# motor-1.net
KiCad netlist of a schematic drawn in EAGLE
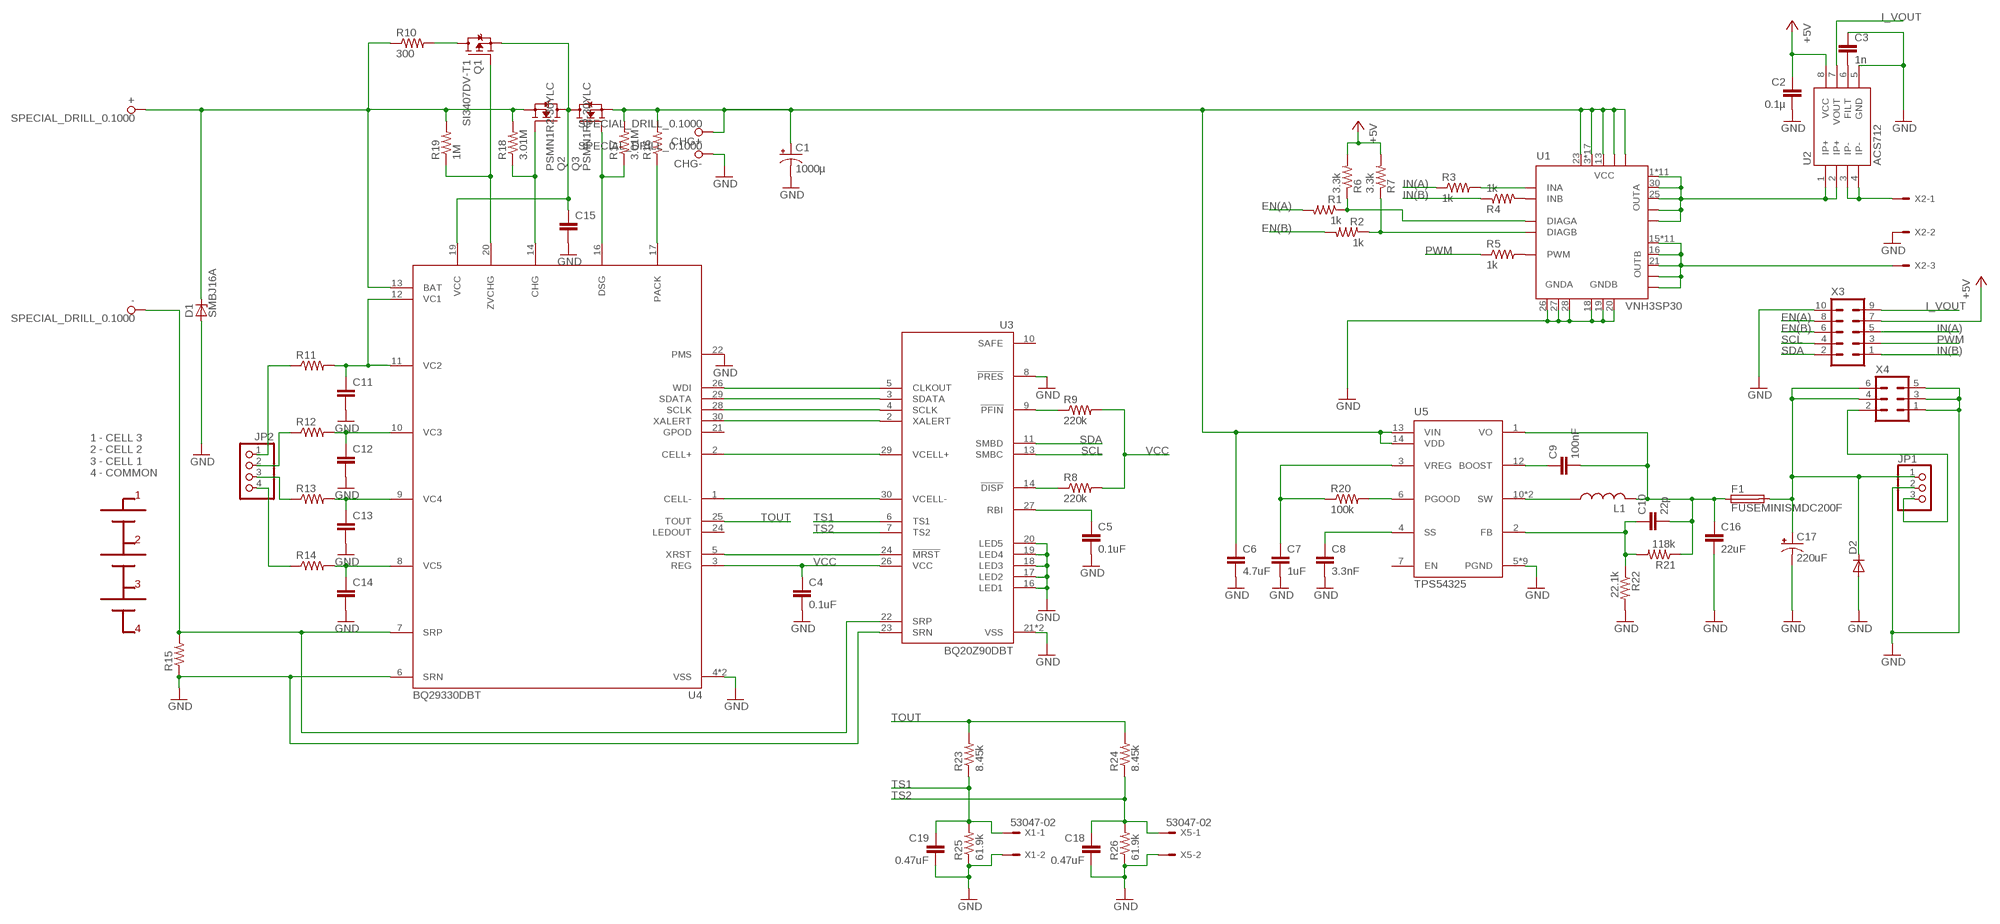
[diagram p0: schematic, sheet 1]

(export (version "E")
  (design (tool "Eeschema 10.0.6"))
  (components
    (comp (ref "+")
      (value "SPECIAL_DRILL_0.1000")
      (footprint "eagle-import:PAD_0.1000")
      (libsource (lib "eagle-import") (part "SPECIAL_DRILL_0.1000"))
    )
    (comp (ref "-")
      (value "SPECIAL_DRILL_0.1000")
      (footprint "eagle-import:PAD_0.1000")
      (libsource (lib "eagle-import") (part "SPECIAL_DRILL_0.1000"))
    )
    (comp (ref "C1")
      (value "1000µ")
      (footprint "eagle-import:E5-13")
      (libsource (lib "eagle-import") (part "CPOL-USE5-13"))
    )
    (comp (ref "C2")
      (value "0.1µ")
      (footprint "eagle-import:C0805")
      (libsource (lib "eagle-import") (part "C-EUC0805"))
    )
    (comp (ref "C3")
      (value "1n")
      (footprint "eagle-import:C0805")
      (libsource (lib "eagle-import") (part "C-EUC0805"))
    )
    (comp (ref "C4")
      (value "0.1uF")
      (footprint "eagle-import:C0603")
      (libsource (lib "eagle-import") (part "C-EUC0603"))
    )
    (comp (ref "C5")
      (value "0.1uF")
      (footprint "eagle-import:C0603")
      (libsource (lib "eagle-import") (part "C-EUC0603"))
    )
    (comp (ref "C6")
      (value "4.7uF")
      (footprint "eagle-import:C1206")
      (libsource (lib "eagle-import") (part "C-EUC1206"))
    )
    (comp (ref "C7")
      (value "1uF")
      (footprint "eagle-import:C0805")
      (libsource (lib "eagle-import") (part "C-EUC0805"))
    )
    (comp (ref "C8")
      (value "3.3nF")
      (footprint "eagle-import:C0805")
      (libsource (lib "eagle-import") (part "C-EUC0805"))
    )
    (comp (ref "C9")
      (value "100nF")
      (footprint "eagle-import:C0805")
      (libsource (lib "eagle-import") (part "C-EUC0805"))
    )
    (comp (ref "C10")
      (value "22p")
      (footprint "eagle-import:C0805")
      (libsource (lib "eagle-import") (part "C-EUC0805"))
    )
    (comp (ref "C11")
      (value "C-EUC0603")
      (footprint "eagle-import:C0603")
      (libsource (lib "eagle-import") (part "C-EUC0603"))
    )
    (comp (ref "C12")
      (value "C-EUC0603")
      (footprint "eagle-import:C0603")
      (libsource (lib "eagle-import") (part "C-EUC0603"))
    )
    (comp (ref "C13")
      (value "C-EUC0603")
      (footprint "eagle-import:C0603")
      (libsource (lib "eagle-import") (part "C-EUC0603"))
    )
    (comp (ref "C14")
      (value "C-EUC0603")
      (footprint "eagle-import:C0603")
      (libsource (lib "eagle-import") (part "C-EUC0603"))
    )
    (comp (ref "C15")
      (value "C-EUC0603")
      (footprint "eagle-import:C0603")
      (libsource (lib "eagle-import") (part "C-EUC0603"))
    )
    (comp (ref "C16")
      (value "22uF")
      (footprint "eagle-import:C3225")
      (libsource (lib "eagle-import") (part "C-EUC3225"))
    )
    (comp (ref "C17")
      (value "220uF")
      (footprint "eagle-import:E3,5-8")
      (libsource (lib "eagle-import") (part "CPOL-USE3.5-8"))
    )
    (comp (ref "C18")
      (value "0.47uF")
      (footprint "eagle-import:C0603")
      (libsource (lib "eagle-import") (part "C-EUC0603"))
    )
    (comp (ref "C19")
      (value "0.47uF")
      (footprint "eagle-import:C0603")
      (libsource (lib "eagle-import") (part "C-EUC0603"))
    )
    (comp (ref "CHG+")
      (value "SPECIAL_DRILL_0.1000")
      (footprint "eagle-import:PAD_0.1000")
      (libsource (lib "eagle-import") (part "SPECIAL_DRILL_0.1000"))
    )
    (comp (ref "CHG-")
      (value "SPECIAL_DRILL_0.1000")
      (footprint "eagle-import:PAD_0.1000")
      (libsource (lib "eagle-import") (part "SPECIAL_DRILL_0.1000"))
    )
    (comp (ref "D1")
      (value "SMBJ16A")
      (footprint "eagle-import:SMB")
      (libsource (lib "eagle-import") (part "ZENER-DIODESMB"))
    )
    (comp (ref "D2")
      (value "DIODE-DO214AC")
      (footprint "eagle-import:DO214AC")
      (libsource (lib "eagle-import") (part "DIODE-DO214AC"))
    )
    (comp (ref "F1")
      (value "FUSEMINISMDC200F")
      (footprint "eagle-import:MINISMDC200F")
      (libsource (lib "eagle-import") (part "FUSEMINISMDC200F"))
    )
    (comp (ref "JP1")
      (value "PINHD-1X3")
      (footprint "eagle-import:1X03")
      (libsource (lib "eagle-import") (part "PINHD-1X3"))
    )
    (comp (ref "JP2")
      (value "PINHD-1X4")
      (footprint "eagle-import:1X04")
      (libsource (lib "eagle-import") (part "PINHD-1X4"))
    )
    (comp (ref "L1")
      (value "L-USXAL50XX")
      (footprint "eagle-import:XAL50XX")
      (libsource (lib "eagle-import") (part "L-USXAL50XX"))
    )
    (comp (ref "Q1")
      (value "SI3407DV-T1")
      (footprint "eagle-import:SOT23-6")
      (libsource (lib "eagle-import") (part "SI3407DV-T1"))
    )
    (comp (ref "Q2")
      (value "PSMN1R2-30YLC")
      (footprint "eagle-import:LFPAK")
      (libsource (lib "eagle-import") (part "PSMN1R2-30YLC"))
    )
    (comp (ref "Q3")
      (value "PSMN1R2-30YLC")
      (footprint "eagle-import:LFPAK")
      (libsource (lib "eagle-import") (part "PSMN1R2-30YLC"))
    )
    (comp (ref "R1")
      (value "1k")
      (footprint "eagle-import:R0805")
      (libsource (lib "eagle-import") (part "R-US_R0805"))
    )
    (comp (ref "R2")
      (value "1k")
      (footprint "eagle-import:R0805")
      (libsource (lib "eagle-import") (part "R-US_R0805"))
    )
    (comp (ref "R3")
      (value "1k")
      (footprint "eagle-import:R0805")
      (libsource (lib "eagle-import") (part "R-US_R0805"))
    )
    (comp (ref "R4")
      (value "1k")
      (footprint "eagle-import:R0805")
      (libsource (lib "eagle-import") (part "R-US_R0805"))
    )
    (comp (ref "R5")
      (value "1k")
      (footprint "eagle-import:R0805")
      (libsource (lib "eagle-import") (part "R-US_R0805"))
    )
    (comp (ref "R6")
      (value "3.3k")
      (footprint "eagle-import:R0805")
      (libsource (lib "eagle-import") (part "R-US_R0805"))
    )
    (comp (ref "R7")
      (value "3.3k")
      (footprint "eagle-import:R0805")
      (libsource (lib "eagle-import") (part "R-US_R0805"))
    )
    (comp (ref "R8")
      (value "220k")
      (footprint "eagle-import:R0603")
      (libsource (lib "eagle-import") (part "R-US_R0603"))
    )
    (comp (ref "R9")
      (value "220k")
      (footprint "eagle-import:R0603")
      (libsource (lib "eagle-import") (part "R-US_R0603"))
    )
    (comp (ref "R10")
      (value "300")
      (footprint "eagle-import:R2512")
      (libsource (lib "eagle-import") (part "R-US_R2512"))
    )
    (comp (ref "R11")
      (value "R-US_R0603")
      (footprint "eagle-import:R0603")
      (libsource (lib "eagle-import") (part "R-US_R0603"))
    )
    (comp (ref "R12")
      (value "R-US_R0603")
      (footprint "eagle-import:R0603")
      (libsource (lib "eagle-import") (part "R-US_R0603"))
    )
    (comp (ref "R13")
      (value "R-US_R0603")
      (footprint "eagle-import:R0603")
      (libsource (lib "eagle-import") (part "R-US_R0603"))
    )
    (comp (ref "R14")
      (value "R-US_R0603")
      (footprint "eagle-import:R0603")
      (libsource (lib "eagle-import") (part "R-US_R0603"))
    )
    (comp (ref "R15")
      (value "R-US_R1210")
      (footprint "eagle-import:R1210")
      (libsource (lib "eagle-import") (part "R-US_R1210"))
    )
    (comp (ref "R16")
      (value "R-US_R0603")
      (footprint "eagle-import:R0603")
      (libsource (lib "eagle-import") (part "R-US_R0603"))
    )
    (comp (ref "R17")
      (value "3.01M")
      (footprint "eagle-import:R0603")
      (libsource (lib "eagle-import") (part "R-US_R0603"))
    )
    (comp (ref "R18")
      (value "3.01M")
      (footprint "eagle-import:R0603")
      (libsource (lib "eagle-import") (part "R-US_R0603"))
    )
    (comp (ref "R19")
      (value "1M")
      (footprint "eagle-import:R0603")
      (libsource (lib "eagle-import") (part "R-US_R0603"))
    )
    (comp (ref "R20")
      (value "100k")
      (footprint "eagle-import:R0805")
      (libsource (lib "eagle-import") (part "R-US_R0805"))
    )
    (comp (ref "R21")
      (value "118k")
      (footprint "eagle-import:R0805")
      (libsource (lib "eagle-import") (part "R-US_R0805"))
    )
    (comp (ref "R22")
      (value "22.1k")
      (footprint "eagle-import:R0805")
      (libsource (lib "eagle-import") (part "R-US_R0805"))
    )
    (comp (ref "R23")
      (value "8.45k")
      (footprint "eagle-import:R0603")
      (libsource (lib "eagle-import") (part "R-US_R0603"))
    )
    (comp (ref "R24")
      (value "8.45k")
      (footprint "eagle-import:R0603")
      (libsource (lib "eagle-import") (part "R-US_R0603"))
    )
    (comp (ref "R25")
      (value "61.9k")
      (footprint "eagle-import:R0603")
      (libsource (lib "eagle-import") (part "R-US_R0603"))
    )
    (comp (ref "R26")
      (value "61.9k")
      (footprint "eagle-import:R0603")
      (libsource (lib "eagle-import") (part "R-US_R0603"))
    )
    (comp (ref "U1")
      (value "VNH3SP30")
      (footprint "eagle-import:MULTIPOWERSO-30")
      (fields (field (name "MPN") "VNH3SP30-E"))
      (libsource (lib "eagle-import") (part "VNH3SP30"))
    )
    (comp (ref "U2")
      (value "ACS712")
      (footprint "eagle-import:SO08")
      (libsource (lib "eagle-import") (part "ACS712"))
    )
    (comp (ref "U3")
      (value "BQ20Z90DBT")
      (footprint "eagle-import:DBT_R-PDSO-G30")
      (libsource (lib "eagle-import") (part "BQ20Z90DBT"))
    )
    (comp (ref "U4")
      (value "BQ29330DBT")
      (footprint "eagle-import:DBT_R-PDSO-G30")
      (libsource (lib "eagle-import") (part "BQ29330DBT"))
    )
    (comp (ref "U5")
      (value "TPS54325")
      (footprint "eagle-import:HTSSOP14PWP")
      (libsource (lib "eagle-import") (part "TPS54325"))
    )
    (comp (ref "X1")
      (value "53047-02")
      (footprint "eagle-import:53047-02")
      (fields (field (name "MF") "MOLEX") (field (name "MPN") "53047-0210"))
      (libsource (lib "eagle-import") (part "53?-02047"))
    )
    (comp (ref "X2")
      (value "KK-156-3")
      (footprint "eagle-import:KK-156-3")
      (libsource (lib "eagle-import") (part "KK-156-3"))
    )
    (comp (ref "X3")
      (value "ML10")
      (footprint "eagle-import:ML10")
      (libsource (lib "eagle-import") (part "ML10"))
    )
    (comp (ref "X4")
      (value "ML6")
      (footprint "eagle-import:ML6")
      (libsource (lib "eagle-import") (part "ML6"))
    )
    (comp (ref "X5")
      (value "53047-02")
      (footprint "eagle-import:53047-02")
      (fields (field (name "MF") "MOLEX") (field (name "MPN") "53047-0210"))
      (libsource (lib "eagle-import") (part "53?-02047"))
    )
  )
  (nets
    (net (code "1") (name "+5V") (class "Default")
      (node (ref "C2") (pin "1") (pinfunction "1_1") (pintype "passive"))
      (node (ref "R6") (pin "2") (pinfunction "2_2") (pintype "passive"))
      (node (ref "R7") (pin "2") (pinfunction "2_2") (pintype "passive"))
      (node (ref "U2") (pin "8") (pinfunction "VCC_8") (pintype "bidirectional"))
      (node (ref "X3") (pin "7") (pinfunction "7_7") (pintype "passive"))
    )
    (net (code "2") (name "/EN(A)") (class "Default")
      (node (ref "R1") (pin "2") (pinfunction "2_2") (pintype "passive"))
      (node (ref "X3") (pin "8") (pinfunction "8_8") (pintype "passive"))
    )
    (net (code "3") (name "/EN(B)") (class "Default")
      (node (ref "R2") (pin "2") (pinfunction "2_2") (pintype "passive"))
      (node (ref "X3") (pin "6") (pinfunction "6_6") (pintype "passive"))
    )
    (net (code "4") (name "/IN(A)") (class "Default")
      (node (ref "R3") (pin "1") (pinfunction "1_1") (pintype "passive"))
      (node (ref "X3") (pin "5") (pinfunction "5_5") (pintype "passive"))
    )
    (net (code "5") (name "/IN(B)") (class "Default")
      (node (ref "R4") (pin "1") (pinfunction "1_1") (pintype "passive"))
      (node (ref "X3") (pin "1") (pinfunction "1_1") (pintype "passive"))
    )
    (net (code "6") (name "/I_VOUT") (class "Default")
      (node (ref "U2") (pin "7") (pinfunction "VOUT_7") (pintype "bidirectional"))
      (node (ref "X3") (pin "9") (pinfunction "9_9") (pintype "passive"))
    )
    (net (code "7") (name "/PWM") (class "Default")
      (node (ref "R5") (pin "1") (pinfunction "1_1") (pintype "passive"))
      (node (ref "X3") (pin "3") (pinfunction "3_3") (pintype "passive"))
    )
    (net (code "8") (name "/SCL") (class "Default")
      (node (ref "U3") (pin "13") (pinfunction "SMBC_13") (pintype "bidirectional"))
      (node (ref "X3") (pin "4") (pinfunction "4_4") (pintype "passive"))
    )
    (net (code "9") (name "/SDA") (class "Default")
      (node (ref "U3") (pin "11") (pinfunction "SMBD_11") (pintype "bidirectional"))
      (node (ref "X3") (pin "2") (pinfunction "2_2") (pintype "passive"))
    )
    (net (code "10") (name "/TOUT") (class "Default")
      (node (ref "R23") (pin "2") (pinfunction "2_2") (pintype "passive"))
      (node (ref "R24") (pin "2") (pinfunction "2_2") (pintype "passive"))
      (node (ref "U4") (pin "25") (pinfunction "TOUT_25") (pintype "bidirectional"))
    )
    (net (code "11") (name "/TS1") (class "Default")
      (node (ref "C19") (pin "1") (pinfunction "1_1") (pintype "passive"))
      (node (ref "R23") (pin "1") (pinfunction "1_1") (pintype "passive"))
      (node (ref "R25") (pin "2") (pinfunction "2_2") (pintype "passive"))
      (node (ref "U3") (pin "6") (pinfunction "TS1_6") (pintype "bidirectional"))
      (node (ref "X1") (pin "1") (pinfunction "S_1") (pintype "passive"))
    )
    (net (code "12") (name "/TS2") (class "Default")
      (node (ref "C18") (pin "1") (pinfunction "1_1") (pintype "passive"))
      (node (ref "R24") (pin "1") (pinfunction "1_1") (pintype "passive"))
      (node (ref "R26") (pin "2") (pinfunction "2_2") (pintype "passive"))
      (node (ref "U3") (pin "7") (pinfunction "TS2_7") (pintype "bidirectional"))
      (node (ref "X5") (pin "1") (pinfunction "S_1") (pintype "passive"))
    )
    (net (code "13") (name "/VCC") (class "Default")
      (node (ref "C4") (pin "1") (pinfunction "1_1") (pintype "passive"))
      (node (ref "R8") (pin "2") (pinfunction "2_2") (pintype "passive"))
      (node (ref "R9") (pin "2") (pinfunction "2_2") (pintype "passive"))
      (node (ref "U3") (pin "26") (pinfunction "VCC_26") (pintype "bidirectional"))
      (node (ref "U4") (pin "3") (pinfunction "REG_3") (pintype "bidirectional"))
    )
    (net (code "14") (name "GND") (class "Default")
      (node (ref "C1") (pin "-") (pinfunction "-_-") (pintype "passive"))
      (node (ref "C11") (pin "2") (pinfunction "2_2") (pintype "passive"))
      (node (ref "C12") (pin "2") (pinfunction "2_2") (pintype "passive"))
      (node (ref "C13") (pin "2") (pinfunction "2_2") (pintype "passive"))
      (node (ref "C14") (pin "2") (pinfunction "2_2") (pintype "passive"))
      (node (ref "C15") (pin "2") (pinfunction "2_2") (pintype "passive"))
      (node (ref "C16") (pin "2") (pinfunction "2_2") (pintype "passive"))
      (node (ref "C17") (pin "-") (pinfunction "-_-") (pintype "passive"))
      (node (ref "C18") (pin "2") (pinfunction "2_2") (pintype "passive"))
      (node (ref "C19") (pin "2") (pinfunction "2_2") (pintype "passive"))
      (node (ref "C2") (pin "2") (pinfunction "2_2") (pintype "passive"))
      (node (ref "C3") (pin "1") (pinfunction "1_1") (pintype "passive"))
      (node (ref "C4") (pin "2") (pinfunction "2_2") (pintype "passive"))
      (node (ref "C5") (pin "2") (pinfunction "2_2") (pintype "passive"))
      (node (ref "C6") (pin "2") (pinfunction "2_2") (pintype "passive"))
      (node (ref "C7") (pin "2") (pinfunction "2_2") (pintype "passive"))
      (node (ref "C8") (pin "2") (pinfunction "2_2") (pintype "passive"))
      (node (ref "CHG-") (pin "1") (pinfunction "1_1") (pintype "passive"))
      (node (ref "D1") (pin "A") (pinfunction "A_A") (pintype "passive"))
      (node (ref "D2") (pin "A") (pinfunction "A_A") (pintype "passive"))
      (node (ref "JP1") (pin "2") (pinfunction "2_2") (pintype "passive"))
      (node (ref "R15") (pin "1") (pinfunction "1_1") (pintype "passive"))
      (node (ref "R22") (pin "2") (pinfunction "2_2") (pintype "passive"))
      (node (ref "R25") (pin "1") (pinfunction "1_1") (pintype "passive"))
      (node (ref "R26") (pin "1") (pinfunction "1_1") (pintype "passive"))
      (node (ref "U1") (pin "18") (pinfunction "GNDB_18") (pintype "power_in"))
      (node (ref "U1") (pin "19") (pinfunction "GNDB_19") (pintype "power_in"))
      (node (ref "U1") (pin "20") (pinfunction "GNDB_20") (pintype "power_in"))
      (node (ref "U1") (pin "26") (pinfunction "GNDA_26") (pintype "power_in"))
      (node (ref "U1") (pin "27") (pinfunction "GNDA_27") (pintype "power_in"))
      (node (ref "U1") (pin "28") (pinfunction "GNDA_28") (pintype "power_in"))
      (node (ref "U2") (pin "5") (pinfunction "GND_5") (pintype "bidirectional"))
      (node (ref "U3") (pin "16") (pinfunction "LED1_16") (pintype "bidirectional"))
      (node (ref "U3") (pin "17") (pinfunction "LED2_17") (pintype "bidirectional"))
      (node (ref "U3") (pin "18") (pinfunction "LED3_18") (pintype "bidirectional"))
      (node (ref "U3") (pin "19") (pinfunction "LED4_19") (pintype "bidirectional"))
      (node (ref "U3") (pin "20") (pinfunction "LED5_20") (pintype "bidirectional"))
      (node (ref "U3") (pin "21") (pinfunction "VSS_21") (pintype "bidirectional"))
      (node (ref "U3") (pin "23") (pinfunction "SRN_23") (pintype "bidirectional"))
      (node (ref "U3") (pin "25") (pinfunction "VSS_25") (pintype "bidirectional"))
      (node (ref "U3") (pin "8") (pinfunction "~{PRES}_8") (pintype "bidirectional"))
      (node (ref "U4") (pin "22") (pinfunction "PMS_22") (pintype "bidirectional"))
      (node (ref "U4") (pin "23") (pinfunction "VSS_23") (pintype "bidirectional"))
      (node (ref "U4") (pin "4") (pinfunction "VSS_4") (pintype "bidirectional"))
      (node (ref "U4") (pin "6") (pinfunction "SRN_6") (pintype "bidirectional"))
      (node (ref "U5") (pin "5") (pinfunction "PGND_5") (pintype "bidirectional"))
      (node (ref "U5") (pin "8") (pinfunction "PGND_8") (pintype "bidirectional"))
      (node (ref "U5") (pin "9") (pinfunction "PGND_9") (pintype "bidirectional"))
      (node (ref "U5") (pin "EXP") (pinfunction "PGND_EXP") (pintype "bidirectional"))
      (node (ref "U5") (pin "EXP1") (pinfunction "PGND_EXP1") (pintype "bidirectional"))
      (node (ref "U5") (pin "P$1") (pinfunction "PGND_P$1") (pintype "bidirectional"))
      (node (ref "U5") (pin "P$2") (pinfunction "PGND_P$2") (pintype "bidirectional"))
      (node (ref "U5") (pin "P$3") (pinfunction "PGND_P$3") (pintype "bidirectional"))
      (node (ref "U5") (pin "P$4") (pinfunction "PGND_P$4") (pintype "bidirectional"))
      (node (ref "X1") (pin "2") (pinfunction "S_2") (pintype "passive"))
      (node (ref "X2") (pin "2") (pinfunction "S_2") (pintype "passive"))
      (node (ref "X3") (pin "10") (pinfunction "10_10") (pintype "passive"))
      (node (ref "X4") (pin "1") (pinfunction "1_1") (pintype "passive"))
      (node (ref "X4") (pin "3") (pinfunction "3_3") (pintype "passive"))
      (node (ref "X4") (pin "5") (pinfunction "5_5") (pintype "passive"))
      (node (ref "X5") (pin "2") (pinfunction "S_2") (pintype "passive"))
    )
    (net (code "15") (name "Net-(C17-Pad+)") (class "Default")
      (node (ref "C17") (pin "+") (pinfunction "+_+") (pintype "passive"))
      (node (ref "D2") (pin "C") (pinfunction "C_C") (pintype "passive"))
      (node (ref "F1") (pin "2") (pinfunction "2_2") (pintype "passive"))
      (node (ref "JP1") (pin "1") (pinfunction "1_1") (pintype "passive"))
      (node (ref "X4") (pin "4") (pinfunction "4_4") (pintype "passive"))
      (node (ref "X4") (pin "6") (pinfunction "6_6") (pintype "passive"))
    )
    (net (code "16") (name "Net-(JP1-Pad3)") (class "Default")
      (node (ref "JP1") (pin "3") (pinfunction "3_3") (pintype "passive"))
      (node (ref "X4") (pin "2") (pinfunction "2_2") (pintype "passive"))
    )
    (net (code "17") (name "Net-(JP2-Pad1)") (class "Default")
      (node (ref "JP2") (pin "1") (pinfunction "1_1") (pintype "passive"))
      (node (ref "R11") (pin "1") (pinfunction "1_1") (pintype "passive"))
    )
    (net (code "18") (name "Net-(JP2-Pad2)") (class "Default")
      (node (ref "JP2") (pin "2") (pinfunction "2_2") (pintype "passive"))
      (node (ref "R12") (pin "1") (pinfunction "1_1") (pintype "passive"))
    )
    (net (code "19") (name "Net-(JP2-Pad3)") (class "Default")
      (node (ref "JP2") (pin "3") (pinfunction "3_3") (pintype "passive"))
      (node (ref "R13") (pin "1") (pinfunction "1_1") (pintype "passive"))
    )
    (net (code "20") (name "Net-(JP2-Pad4)") (class "Default")
      (node (ref "JP2") (pin "4") (pinfunction "4_4") (pintype "passive"))
      (node (ref "R14") (pin "1") (pinfunction "1_1") (pintype "passive"))
    )
    (net (code "21") (name "Net-(L1-Pad1)") (class "Default")
      (node (ref "L1") (pin "1") (pinfunction "1_1") (pintype "passive"))
      (node (ref "U5") (pin "10") (pinfunction "SW_10") (pintype "bidirectional"))
      (node (ref "U5") (pin "11") (pinfunction "SW_11") (pintype "bidirectional"))
    )
    (net (code "22") (name "Net-(Q1-D1-Pad1)") (class "Default")
      (node (ref "Q1") (pin "1") (pinfunction "D1_1") (pintype "passive"))
      (node (ref "Q1") (pin "2") (pinfunction "D1_2") (pintype "passive"))
      (node (ref "Q1") (pin "5") (pinfunction "D1_5") (pintype "passive"))
      (node (ref "Q1") (pin "6") (pinfunction "D1_6") (pintype "passive"))
      (node (ref "R10") (pin "2") (pinfunction "2_2") (pintype "passive"))
    )
    (net (code "23") (name "Net-(Q1-G1)") (class "Default")
      (node (ref "Q1") (pin "3") (pinfunction "G1_3") (pintype "passive"))
      (node (ref "R19") (pin "1") (pinfunction "1_1") (pintype "passive"))
      (node (ref "U4") (pin "20") (pinfunction "ZVCHG_20") (pintype "bidirectional"))
    )
    (net (code "24") (name "Net-(Q1-S1)") (class "Default")
      (node (ref "C15") (pin "1") (pinfunction "1_1") (pintype "passive"))
      (node (ref "Q1") (pin "4") (pinfunction "S1_4") (pintype "passive"))
      (node (ref "Q2") (pin "P$1") (pinfunction "D_P$1") (pintype "passive"))
      (node (ref "Q2") (pin "P$2") (pinfunction "D_P$2") (pintype "passive"))
      (node (ref "Q2") (pin "P$3") (pinfunction "D_P$3") (pintype "passive"))
      (node (ref "Q3") (pin "P$1") (pinfunction "D_P$1") (pintype "passive"))
      (node (ref "Q3") (pin "P$2") (pinfunction "D_P$2") (pintype "passive"))
      (node (ref "Q3") (pin "P$3") (pinfunction "D_P$3") (pintype "passive"))
      (node (ref "U4") (pin "19") (pinfunction "VCC_19") (pintype "bidirectional"))
    )
    (net (code "25") (name "Net-(Q2-G)") (class "Default")
      (node (ref "Q2") (pin "4") (pinfunction "G_4") (pintype "passive"))
      (node (ref "R18") (pin "1") (pinfunction "1_1") (pintype "passive"))
      (node (ref "U4") (pin "14") (pinfunction "CHG_14") (pintype "bidirectional"))
    )
    (net (code "26") (name "Net-(Q3-G)") (class "Default")
      (node (ref "Q3") (pin "4") (pinfunction "G_4") (pintype "passive"))
      (node (ref "R17") (pin "1") (pinfunction "1_1") (pintype "passive"))
      (node (ref "U4") (pin "16") (pinfunction "DSG_16") (pintype "bidirectional"))
    )
    (net (code "27") (name "Net-(U1-DIAGA)") (class "Default")
      (node (ref "R1") (pin "1") (pinfunction "1_1") (pintype "passive"))
      (node (ref "R6") (pin "1") (pinfunction "1_1") (pintype "passive"))
      (node (ref "U1") (pin "6") (pinfunction "DIAGA_6") (pintype "open_collector"))
    )
    (net (code "28") (name "Net-(U1-DIAGB)") (class "Default")
      (node (ref "R2") (pin "1") (pinfunction "1_1") (pintype "passive"))
      (node (ref "R7") (pin "1") (pinfunction "1_1") (pintype "passive"))
      (node (ref "U1") (pin "10") (pinfunction "DIAGB_10") (pintype "open_collector"))
    )
    (net (code "29") (name "Net-(U1-INA)") (class "Default")
      (node (ref "R3") (pin "2") (pinfunction "2_2") (pintype "passive"))
      (node (ref "U1") (pin "5") (pinfunction "INA_5") (pintype "input"))
    )
    (net (code "30") (name "Net-(U1-INB)") (class "Default")
      (node (ref "R4") (pin "2") (pinfunction "2_2") (pintype "passive"))
      (node (ref "U1") (pin "11") (pinfunction "INB_11") (pintype "input"))
    )
    (net (code "31") (name "Net-(U1-OUTA-Pad1)") (class "Default")
      (node (ref "U1") (pin "1") (pinfunction "OUTA_1") (pintype "output"))
      (node (ref "U1") (pin "25") (pinfunction "OUTA_25") (pintype "passive"))
      (node (ref "U1") (pin "30") (pinfunction "OUTA_30") (pintype "passive"))
      (node (ref "U1") (pin "OUTA") (pinfunction "OUTA_OUTA") (pintype "passive"))
      (node (ref "U1") (pin "OUTA1") (pinfunction "OUTA_OUTA1") (pintype "output"))
      (node (ref "U1") (pin "OUTA10") (pinfunction "OUTA_OUTA10") (pintype "output"))
      (node (ref "U1") (pin "OUTA2") (pinfunction "OUTA_OUTA2") (pintype "output"))
      (node (ref "U1") (pin "OUTA3") (pinfunction "OUTA_OUTA3") (pintype "output"))
      (node (ref "U1") (pin "OUTA4") (pinfunction "OUTA_OUTA4") (pintype "output"))
      (node (ref "U1") (pin "OUTA5") (pinfunction "OUTA_OUTA5") (pintype "output"))
      (node (ref "U1") (pin "OUTA6") (pinfunction "OUTA_OUTA6") (pintype "output"))
      (node (ref "U1") (pin "OUTA7") (pinfunction "OUTA_OUTA7") (pintype "output"))
      (node (ref "U1") (pin "OUTA8") (pinfunction "OUTA_OUTA8") (pintype "output"))
      (node (ref "U1") (pin "OUTA9") (pinfunction "OUTA_OUTA9") (pintype "output"))
      (node (ref "U1") (pin "OUTA@1") (pinfunction "OUTA_OUTA@1") (pintype "passive"))
      (node (ref "U2") (pin "1") (pinfunction "IP+_1") (pintype "bidirectional"))
      (node (ref "U2") (pin "2") (pinfunction "IP+_2") (pintype "bidirectional"))
    )
    (net (code "32") (name "Net-(U1-PWM)") (class "Default")
      (node (ref "R5") (pin "2") (pinfunction "2_2") (pintype "passive"))
      (node (ref "U1") (pin "8") (pinfunction "PWM_8") (pintype "input"))
    )
    (net (code "33") (name "Net-(U2-FILT)") (class "Default")
      (node (ref "C3") (pin "2") (pinfunction "2_2") (pintype "passive"))
      (node (ref "U2") (pin "6") (pinfunction "FILT_6") (pintype "bidirectional"))
    )
    (net (code "34") (name "Net-(U3-CLKOUT)") (class "Default")
      (node (ref "U3") (pin "5") (pinfunction "CLKOUT_5") (pintype "bidirectional"))
      (node (ref "U4") (pin "26") (pinfunction "WDI_26") (pintype "bidirectional"))
    )
    (net (code "35") (name "Net-(U3-RBI)") (class "Default")
      (node (ref "C5") (pin "1") (pinfunction "1_1") (pintype "passive"))
      (node (ref "U3") (pin "27") (pinfunction "RBI_27") (pintype "bidirectional"))
    )
    (net (code "36") (name "Net-(U3-SCLK)") (class "Default")
      (node (ref "U3") (pin "4") (pinfunction "SCLK_4") (pintype "bidirectional"))
      (node (ref "U4") (pin "28") (pinfunction "SCLK_28") (pintype "bidirectional"))
    )
    (net (code "37") (name "Net-(U3-SDATA)") (class "Default")
      (node (ref "U3") (pin "3") (pinfunction "SDATA_3") (pintype "bidirectional"))
      (node (ref "U4") (pin "29") (pinfunction "SDATA_29") (pintype "bidirectional"))
    )
    (net (code "38") (name "Net-(U3-SRP)") (class "Default")
      (node (ref "-") (pin "1") (pinfunction "1_1") (pintype "passive"))
      (node (ref "R15") (pin "2") (pinfunction "2_2") (pintype "passive"))
      (node (ref "U3") (pin "22") (pinfunction "SRP_22") (pintype "bidirectional"))
      (node (ref "U4") (pin "7") (pinfunction "SRP_7") (pintype "bidirectional"))
    )
    (net (code "39") (name "Net-(U3-VCELL+)") (class "Default")
      (node (ref "U3") (pin "29") (pinfunction "VCELL+_29") (pintype "bidirectional"))
      (node (ref "U4") (pin "2") (pinfunction "CELL+_2") (pintype "bidirectional"))
    )
    (net (code "40") (name "Net-(U3-VCELL-)") (class "Default")
      (node (ref "U3") (pin "30") (pinfunction "VCELL-_30") (pintype "bidirectional"))
      (node (ref "U4") (pin "1") (pinfunction "CELL-_1") (pintype "bidirectional"))
    )
    (net (code "41") (name "Net-(U3-XALERT)") (class "Default")
      (node (ref "U3") (pin "2") (pinfunction "XALERT_2") (pintype "bidirectional"))
      (node (ref "U4") (pin "30") (pinfunction "XALERT_30") (pintype "bidirectional"))
    )
    (net (code "42") (name "Net-(U3-~{DISP})") (class "Default")
      (node (ref "R8") (pin "1") (pinfunction "1_1") (pintype "passive"))
      (node (ref "U3") (pin "14") (pinfunction "~{DISP}_14") (pintype "bidirectional"))
    )
    (net (code "43") (name "Net-(U3-~{MRST})") (class "Default")
      (node (ref "U3") (pin "24") (pinfunction "~{MRST}_24") (pintype "bidirectional"))
      (node (ref "U4") (pin "5") (pinfunction "XRST_5") (pintype "bidirectional"))
    )
    (net (code "44") (name "Net-(U3-~{PFIN})") (class "Default")
      (node (ref "R9") (pin "1") (pinfunction "1_1") (pintype "passive"))
      (node (ref "U3") (pin "9") (pinfunction "~{PFIN}_9") (pintype "bidirectional"))
    )
    (net (code "45") (name "Net-(U4-BAT)") (class "Default")
      (node (ref "+") (pin "1") (pinfunction "1_1") (pintype "passive"))
      (node (ref "D1") (pin "C") (pinfunction "C_C") (pintype "passive"))
      (node (ref "Q2") (pin "1") (pinfunction "S_1") (pintype "passive"))
      (node (ref "Q2") (pin "2") (pinfunction "S_2") (pintype "passive"))
      (node (ref "Q2") (pin "3") (pinfunction "S_3") (pintype "passive"))
      (node (ref "R10") (pin "1") (pinfunction "1_1") (pintype "passive"))
      (node (ref "R18") (pin "2") (pinfunction "2_2") (pintype "passive"))
      (node (ref "R19") (pin "2") (pinfunction "2_2") (pintype "passive"))
      (node (ref "U4") (pin "13") (pinfunction "BAT_13") (pintype "bidirectional"))
    )
    (net (code "46") (name "Net-(U4-PACK)") (class "Default")
      (node (ref "R16") (pin "1") (pinfunction "1_1") (pintype "passive"))
      (node (ref "U4") (pin "17") (pinfunction "PACK_17") (pintype "bidirectional"))
    )
    (net (code "47") (name "Net-(U4-VC1)") (class "Default")
      (node (ref "C11") (pin "1") (pinfunction "1_1") (pintype "passive"))
      (node (ref "R11") (pin "2") (pinfunction "2_2") (pintype "passive"))
      (node (ref "U4") (pin "11") (pinfunction "VC2_11") (pintype "bidirectional"))
      (node (ref "U4") (pin "12") (pinfunction "VC1_12") (pintype "bidirectional"))
    )
    (net (code "48") (name "Net-(U4-VC3)") (class "Default")
      (node (ref "C12") (pin "1") (pinfunction "1_1") (pintype "passive"))
      (node (ref "R12") (pin "2") (pinfunction "2_2") (pintype "passive"))
      (node (ref "U4") (pin "10") (pinfunction "VC3_10") (pintype "bidirectional"))
    )
    (net (code "49") (name "Net-(U4-VC4)") (class "Default")
      (node (ref "C13") (pin "1") (pinfunction "1_1") (pintype "passive"))
      (node (ref "R13") (pin "2") (pinfunction "2_2") (pintype "passive"))
      (node (ref "U4") (pin "9") (pinfunction "VC4_9") (pintype "bidirectional"))
    )
    (net (code "50") (name "Net-(U4-VC5)") (class "Default")
      (node (ref "C14") (pin "1") (pinfunction "1_1") (pintype "passive"))
      (node (ref "R14") (pin "2") (pinfunction "2_2") (pintype "passive"))
      (node (ref "U4") (pin "8") (pinfunction "VC5_8") (pintype "bidirectional"))
    )
    (net (code "51") (name "Net-(U5-BOOST)") (class "Default")
      (node (ref "C9") (pin "1") (pinfunction "1_1") (pintype "passive"))
      (node (ref "U5") (pin "12") (pinfunction "BOOST_12") (pintype "bidirectional"))
    )
    (net (code "52") (name "Net-(U5-FB)") (class "Default")
      (node (ref "C10") (pin "1") (pinfunction "1_1") (pintype "passive"))
      (node (ref "R21") (pin "2") (pinfunction "2_2") (pintype "passive"))
      (node (ref "R22") (pin "1") (pinfunction "1_1") (pintype "passive"))
      (node (ref "U5") (pin "2") (pinfunction "FB_2") (pintype "bidirectional"))
    )
    (net (code "53") (name "Net-(U5-PGOOD)") (class "Default")
      (node (ref "R20") (pin "2") (pinfunction "2_2") (pintype "passive"))
      (node (ref "U5") (pin "6") (pinfunction "PGOOD_6") (pintype "bidirectional"))
    )
    (net (code "54") (name "Net-(U5-SS)") (class "Default")
      (node (ref "C8") (pin "1") (pinfunction "1_1") (pintype "passive"))
      (node (ref "U5") (pin "4") (pinfunction "SS_4") (pintype "bidirectional"))
    )
    (net (code "55") (name "Net-(U5-VDD)") (class "Default")
      (node (ref "C1") (pin "+") (pinfunction "+_+") (pintype "passive"))
      (node (ref "C6") (pin "1") (pinfunction "1_1") (pintype "passive"))
      (node (ref "CHG+") (pin "1") (pinfunction "1_1") (pintype "passive"))
      (node (ref "Q3") (pin "1") (pinfunction "S_1") (pintype "passive"))
      (node (ref "Q3") (pin "2") (pinfunction "S_2") (pintype "passive"))
      (node (ref "Q3") (pin "3") (pinfunction "S_3") (pintype "passive"))
      (node (ref "R16") (pin "2") (pinfunction "2_2") (pintype "passive"))
      (node (ref "R17") (pin "2") (pinfunction "2_2") (pintype "passive"))
      (node (ref "U1") (pin "13") (pinfunction "VCC_13") (pintype "power_in"))
      (node (ref "U1") (pin "23") (pinfunction "VCC_23") (pintype "power_in"))
      (node (ref "U1") (pin "3") (pinfunction "VCC_3") (pintype "power_in"))
      (node (ref "U1") (pin "VCC") (pinfunction "VCC_VCC") (pintype "power_in"))
      (node (ref "U1") (pin "VCC1") (pinfunction "VCC_VCC1") (pintype "power_in"))
      (node (ref "U1") (pin "VCC10") (pinfunction "VCC_VCC10") (pintype "power_in"))
      (node (ref "U1") (pin "VCC11") (pinfunction "VCC_VCC11") (pintype "power_in"))
      (node (ref "U1") (pin "VCC12") (pinfunction "VCC_VCC12") (pintype "power_in"))
      (node (ref "U1") (pin "VCC13") (pinfunction "VCC_VCC13") (pintype "power_in"))
      (node (ref "U1") (pin "VCC14") (pinfunction "VCC_VCC14") (pintype "power_in"))
      (node (ref "U1") (pin "VCC15") (pinfunction "VCC_VCC15") (pintype "power_in"))
      (node (ref "U1") (pin "VCC16") (pinfunction "VCC_VCC16") (pintype "power_in"))
      (node (ref "U1") (pin "VCC2") (pinfunction "VCC_VCC2") (pintype "power_in"))
      (node (ref "U1") (pin "VCC3") (pinfunction "VCC_VCC3") (pintype "power_in"))
      (node (ref "U1") (pin "VCC4") (pinfunction "VCC_VCC4") (pintype "power_in"))
      (node (ref "U1") (pin "VCC5") (pinfunction "VCC_VCC5") (pintype "power_in"))
      (node (ref "U1") (pin "VCC6") (pinfunction "VCC_VCC6") (pintype "power_in"))
      (node (ref "U1") (pin "VCC7") (pinfunction "VCC_VCC7") (pintype "power_in"))
      (node (ref "U1") (pin "VCC8") (pinfunction "VCC_VCC8") (pintype "power_in"))
      (node (ref "U1") (pin "VCC9") (pinfunction "VCC_VCC9") (pintype "power_in"))
      (node (ref "U1") (pin "VCC@1") (pinfunction "VCC_VCC@1") (pintype "power_in"))
      (node (ref "U5") (pin "13") (pinfunction "VIN_13") (pintype "bidirectional"))
      (node (ref "U5") (pin "14") (pinfunction "VDD_14") (pintype "bidirectional"))
    )
    (net (code "56") (name "Net-(U5-VO)") (class "Default")
      (node (ref "C10") (pin "2") (pinfunction "2_2") (pintype "passive"))
      (node (ref "C16") (pin "1") (pinfunction "1_1") (pintype "passive"))
      (node (ref "C9") (pin "2") (pinfunction "2_2") (pintype "passive"))
      (node (ref "F1") (pin "1") (pinfunction "1_1") (pintype "passive"))
      (node (ref "L1") (pin "2") (pinfunction "2_2") (pintype "passive"))
      (node (ref "R21") (pin "1") (pinfunction "1_1") (pintype "passive"))
      (node (ref "U5") (pin "1") (pinfunction "VO_1") (pintype "bidirectional"))
    )
    (net (code "57") (name "Net-(U5-VREG)") (class "Default")
      (node (ref "C7") (pin "1") (pinfunction "1_1") (pintype "passive"))
      (node (ref "R20") (pin "1") (pinfunction "1_1") (pintype "passive"))
      (node (ref "U5") (pin "3") (pinfunction "VREG_3") (pintype "bidirectional"))
    )
    (net (code "58") (name "Net-(X2A-S)") (class "Default")
      (node (ref "U2") (pin "3") (pinfunction "IP-_3") (pintype "bidirectional"))
      (node (ref "U2") (pin "4") (pinfunction "IP-_4") (pintype "bidirectional"))
      (node (ref "X2") (pin "1") (pinfunction "S_1") (pintype "passive"))
    )
    (net (code "59") (name "Net-(X2C-S)") (class "Default")
      (node (ref "U1") (pin "15") (pinfunction "OUTB_15") (pintype "output"))
      (node (ref "U1") (pin "16") (pinfunction "OUTB_16") (pintype "passive"))
      (node (ref "U1") (pin "21") (pinfunction "OUTB_21") (pintype "passive"))
      (node (ref "U1") (pin "OUTB") (pinfunction "OUTB_OUTB") (pintype "passive"))
      (node (ref "U1") (pin "OUTB1") (pinfunction "OUTB_OUTB1") (pintype "output"))
      (node (ref "U1") (pin "OUTB10") (pinfunction "OUTB_OUTB10") (pintype "output"))
      (node (ref "U1") (pin "OUTB2") (pinfunction "OUTB_OUTB2") (pintype "output"))
      (node (ref "U1") (pin "OUTB3") (pinfunction "OUTB_OUTB3") (pintype "output"))
      (node (ref "U1") (pin "OUTB4") (pinfunction "OUTB_OUTB4") (pintype "output"))
      (node (ref "U1") (pin "OUTB5") (pinfunction "OUTB_OUTB5") (pintype "output"))
      (node (ref "U1") (pin "OUTB6") (pinfunction "OUTB_OUTB6") (pintype "output"))
      (node (ref "U1") (pin "OUTB7") (pinfunction "OUTB_OUTB7") (pintype "output"))
      (node (ref "U1") (pin "OUTB8") (pinfunction "OUTB_OUTB8") (pintype "output"))
      (node (ref "U1") (pin "OUTB9") (pinfunction "OUTB_OUTB9") (pintype "output"))
      (node (ref "U1") (pin "OUTB@1") (pinfunction "OUTB_OUTB@1") (pintype "passive"))
      (node (ref "X2") (pin "3") (pinfunction "S_3") (pintype "passive"))
    )
    (net (code "60") (name "unconnected-(U3-SAFE-Pad10)") (class "Default")
      (node (ref "U3") (pin "10") (pinfunction "SAFE_10") (pintype "bidirectional"))
    )
    (net (code "61") (name "unconnected-(U4-GPOD-Pad21)") (class "Default")
      (node (ref "U4") (pin "21") (pinfunction "GPOD_21") (pintype "bidirectional"))
    )
    (net (code "62") (name "unconnected-(U4-LEDOUT-Pad24)") (class "Default")
      (node (ref "U4") (pin "24") (pinfunction "LEDOUT_24") (pintype "bidirectional"))
    )
    (net (code "63") (name "unconnected-(U5-EN-Pad7)") (class "Default")
      (node (ref "U5") (pin "7") (pinfunction "EN_7") (pintype "bidirectional"))
    )
  )
)
